# LCD_Joystick.net
KiCad netlist of a schematic drawn in Altium Designer
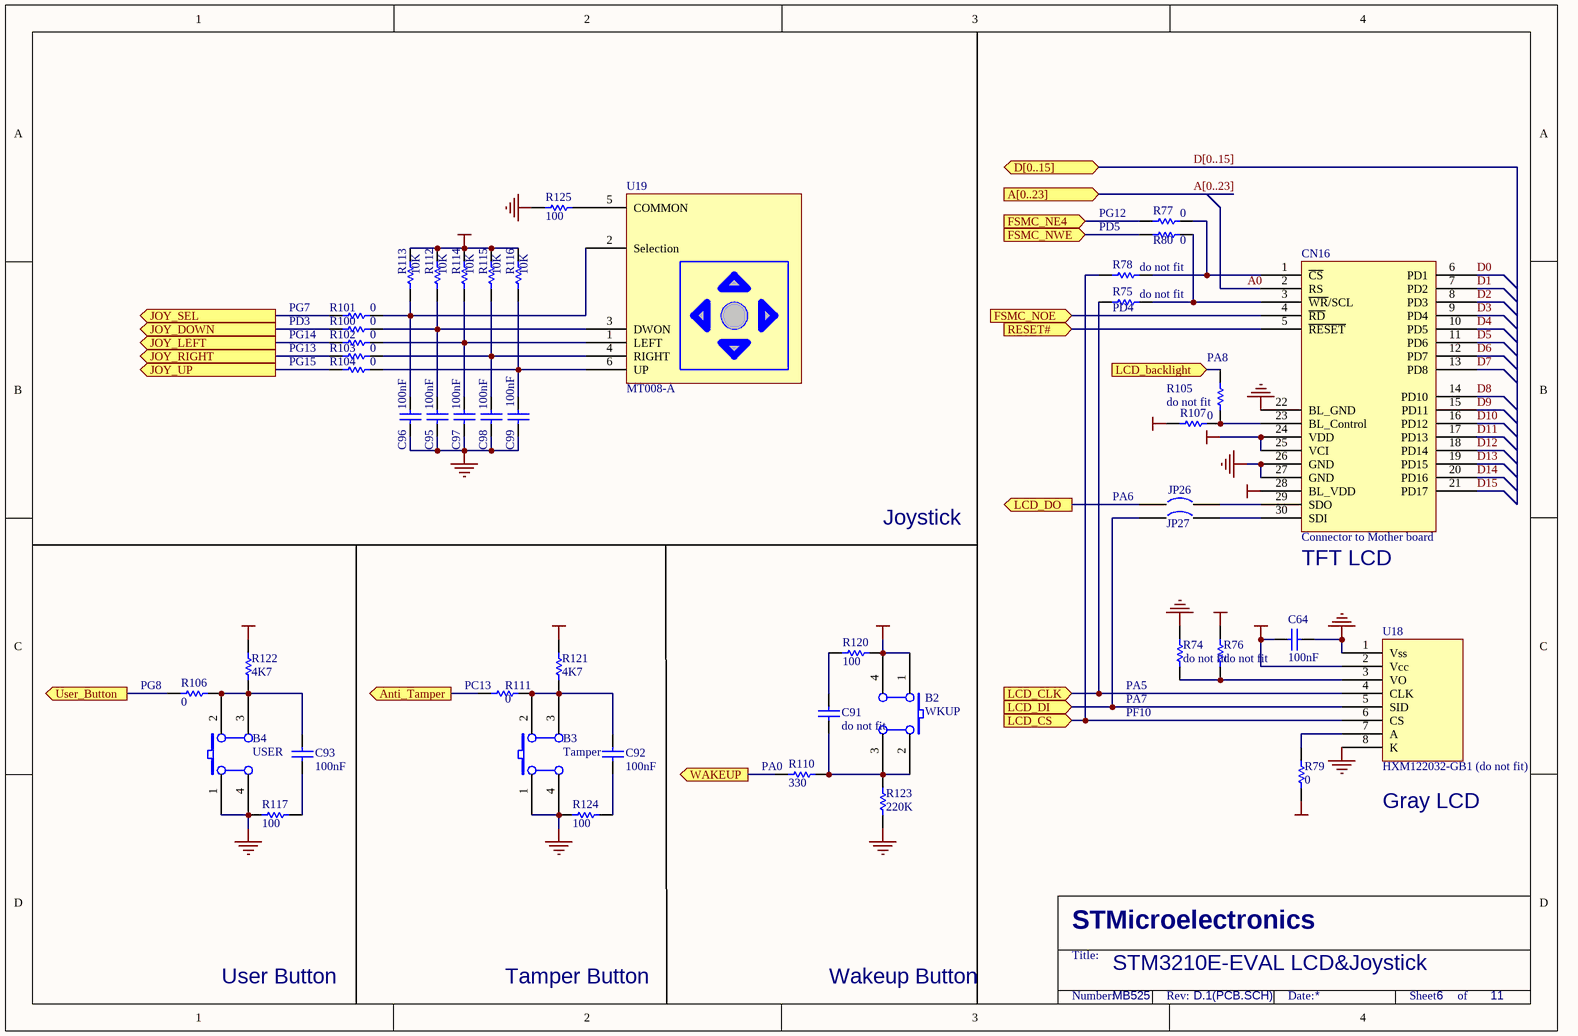
[diagram p0: LCD&Joystick.SchDoc]

(export (version "E")
  (design (tool "Eeschema 10.0.6"))
  (components
    (comp (ref "B2")
      (value "WKUP")
      (footprint "PB10")
      (description "SE PUSHBUTTON")
      (libsource (lib "Documents") (part "SW PUSHBUTTON"))
    )
    (comp (ref "B3")
      (value "Tamper")
      (footprint "PB10")
      (description "SE PUSHBUTTON")
      (libsource (lib "Documents") (part "SW PUSHBUTTON"))
    )
    (comp (ref "B4")
      (value "USER")
      (footprint "PB10")
      (description "SE PUSHBUTTON")
      (libsource (lib "Documents") (part "SW PUSHBUTTON"))
    )
    (comp (ref "C64")
      (value "100nF")
      (description "Capacitor")
      (fields (field (name "PUBLISHER") "Altium Limited"))
      (libsource (lib "Miscellaneous Devices") (part "CAP"))
    )
    (comp (ref "C91")
      (value "do not fit")
      (description "Capacitor")
      (fields (field (name "PUBLISHER") "Altium Limited"))
      (libsource (lib "Miscellaneous Devices") (part "CAP"))
    )
    (comp (ref "C92")
      (value "100nF")
      (description "Capacitor")
      (fields (field (name "PUBLISHER") "Altium Limited"))
      (libsource (lib "Miscellaneous Devices") (part "CAP"))
    )
    (comp (ref "C93")
      (value "100nF")
      (description "Capacitor")
      (fields (field (name "PUBLISHER") "Altium Limited"))
      (libsource (lib "Miscellaneous Devices") (part "CAP"))
    )
    (comp (ref "C95")
      (value "100nF")
      (description "Capacitor")
      (fields (field (name "PUBLISHER") "Altium Limited"))
      (libsource (lib "Miscellaneous Devices") (part "CAP"))
    )
    (comp (ref "C96")
      (value "100nF")
      (description "Capacitor")
      (fields (field (name "PUBLISHER") "Altium Limited"))
      (libsource (lib "Miscellaneous Devices") (part "CAP"))
    )
    (comp (ref "C97")
      (value "100nF")
      (description "Capacitor")
      (fields (field (name "PUBLISHER") "Altium Limited"))
      (libsource (lib "Miscellaneous Devices") (part "CAP"))
    )
    (comp (ref "C98")
      (value "100nF")
      (description "Capacitor")
      (fields (field (name "PUBLISHER") "Altium Limited"))
      (libsource (lib "Miscellaneous Devices") (part "CAP"))
    )
    (comp (ref "C99")
      (value "100nF")
      (description "Capacitor")
      (fields (field (name "PUBLISHER") "Altium Limited"))
      (libsource (lib "Miscellaneous Devices") (part "CAP"))
    )
    (comp (ref "CN16")
      (value "Connector to Mother board")
      (footprint "AM240320A")
      (libsource (lib "MB694") (part "ColorLCD_module"))
    )
    (comp (ref "JP26")
      (value "~")
      (footprint "SPST-2")
      (description "Circuit Breaker")
      (fields (field (name "PUBLISHER") "Altium Limited"))
      (libsource (lib "Miscellaneous Devices") (part "Circuit Breaker"))
    )
    (comp (ref "JP27")
      (value "~")
      (footprint "SPST-2")
      (description "Circuit Breaker")
      (fields (field (name "PUBLISHER") "Altium Limited"))
      (libsource (lib "Miscellaneous Devices") (part "Circuit Breaker"))
    )
    (comp (ref "R74")
      (value "do not fit")
      (description "Resistor")
      (fields (field (name "PUBLISHER") "Altium Limited"))
      (libsource (lib "Miscellaneous Devices") (part "Res1"))
    )
    (comp (ref "R75")
      (value "do not fit")
      (description "Resistor")
      (fields (field (name "PUBLISHER") "Altium Limited"))
      (libsource (lib "Miscellaneous Devices") (part "Res1"))
    )
    (comp (ref "R76")
      (value "do not fit")
      (description "Resistor")
      (fields (field (name "PUBLISHER") "Altium Limited"))
      (libsource (lib "Miscellaneous Devices") (part "Res1"))
    )
    (comp (ref "R77")
      (value "0")
      (description "Resistor")
      (fields (field (name "PUBLISHER") "Altium Limited"))
      (libsource (lib "Miscellaneous Devices") (part "Res1"))
    )
    (comp (ref "R78")
      (value "do not fit")
      (description "Resistor")
      (fields (field (name "PUBLISHER") "Altium Limited"))
      (libsource (lib "Miscellaneous Devices") (part "Res1"))
    )
    (comp (ref "R79")
      (value "0")
      (description "Resistor")
      (fields (field (name "PUBLISHER") "Altium Limited"))
      (libsource (lib "Miscellaneous Devices") (part "Res1"))
    )
    (comp (ref "R80")
      (value "0")
      (description "Resistor")
      (fields (field (name "PUBLISHER") "Altium Limited"))
      (libsource (lib "Miscellaneous Devices") (part "Res1"))
    )
    (comp (ref "R100")
      (value "0")
      (description "Resistor")
      (fields (field (name "PUBLISHER") "Altium Limited"))
      (libsource (lib "Miscellaneous Devices") (part "Res1"))
    )
    (comp (ref "R101")
      (value "0")
      (description "Resistor")
      (fields (field (name "PUBLISHER") "Altium Limited"))
      (libsource (lib "Miscellaneous Devices") (part "Res1"))
    )
    (comp (ref "R102")
      (value "0")
      (description "Resistor")
      (fields (field (name "PUBLISHER") "Altium Limited"))
      (libsource (lib "Miscellaneous Devices") (part "Res1"))
    )
    (comp (ref "R103")
      (value "0")
      (description "Resistor")
      (fields (field (name "PUBLISHER") "Altium Limited"))
      (libsource (lib "Miscellaneous Devices") (part "Res1"))
    )
    (comp (ref "R104")
      (value "0")
      (description "Resistor")
      (fields (field (name "PUBLISHER") "Altium Limited"))
      (libsource (lib "Miscellaneous Devices") (part "Res1"))
    )
    (comp (ref "R105")
      (value "do not fit")
      (description "Resistor")
      (fields (field (name "PUBLISHER") "Altium Limited"))
      (libsource (lib "Miscellaneous Devices") (part "Res1"))
    )
    (comp (ref "R106")
      (value "0")
      (description "Resistor")
      (fields (field (name "PUBLISHER") "Altium Limited"))
      (libsource (lib "Miscellaneous Devices") (part "Res1"))
    )
    (comp (ref "R107")
      (value "0")
      (description "Resistor")
      (fields (field (name "PUBLISHER") "Altium Limited"))
      (libsource (lib "Miscellaneous Devices") (part "Res1"))
    )
    (comp (ref "R110")
      (value "330")
      (description "Resistor")
      (fields (field (name "PUBLISHER") "Altium Limited"))
      (libsource (lib "Miscellaneous Devices") (part "Res1"))
    )
    (comp (ref "R111")
      (value "0")
      (description "Resistor")
      (fields (field (name "PUBLISHER") "Altium Limited"))
      (libsource (lib "Miscellaneous Devices") (part "Res1"))
    )
    (comp (ref "R112")
      (value "10K")
      (description "Resistor")
      (fields (field (name "PUBLISHER") "Altium Limited"))
      (libsource (lib "Miscellaneous Devices") (part "Res1"))
    )
    (comp (ref "R113")
      (value "10K")
      (description "Resistor")
      (fields (field (name "PUBLISHER") "Altium Limited"))
      (libsource (lib "Miscellaneous Devices") (part "Res1"))
    )
    (comp (ref "R114")
      (value "10K")
      (description "Resistor")
      (fields (field (name "PUBLISHER") "Altium Limited"))
      (libsource (lib "Miscellaneous Devices") (part "Res1"))
    )
    (comp (ref "R115")
      (value "10K")
      (description "Resistor")
      (fields (field (name "PUBLISHER") "Altium Limited"))
      (libsource (lib "Miscellaneous Devices") (part "Res1"))
    )
    (comp (ref "R116")
      (value "10K")
      (description "Resistor")
      (fields (field (name "PUBLISHER") "Altium Limited"))
      (libsource (lib "Miscellaneous Devices") (part "Res1"))
    )
    (comp (ref "R117")
      (value "100")
      (description "Resistor")
      (fields (field (name "PUBLISHER") "Altium Limited"))
      (libsource (lib "Miscellaneous Devices") (part "Res1"))
    )
    (comp (ref "R120")
      (value "100")
      (description "Resistor")
      (fields (field (name "PUBLISHER") "Altium Limited"))
      (libsource (lib "Miscellaneous Devices") (part "Res1"))
    )
    (comp (ref "R121")
      (value "4K7")
      (description "Resistor")
      (fields (field (name "PUBLISHER") "Altium Limited"))
      (libsource (lib "Miscellaneous Devices") (part "res1"))
    )
    (comp (ref "R122")
      (value "4K7")
      (description "Resistor")
      (fields (field (name "PUBLISHER") "Altium Limited"))
      (libsource (lib "Miscellaneous Devices") (part "res1"))
    )
    (comp (ref "R123")
      (value "220K")
      (description "Resistor")
      (fields (field (name "PUBLISHER") "Altium Limited"))
      (libsource (lib "Miscellaneous Devices") (part "res1"))
    )
    (comp (ref "R124")
      (value "100")
      (description "Resistor")
      (fields (field (name "PUBLISHER") "Altium Limited"))
      (libsource (lib "Miscellaneous Devices") (part "Res1"))
    )
    (comp (ref "R125")
      (value "100")
      (description "Resistor")
      (fields (field (name "PUBLISHER") "Altium Limited"))
      (libsource (lib "Miscellaneous Devices") (part "Res1"))
    )
    (comp (ref "U18")
      (value "HXM122032-GB1 (do not fit)")
      (footprint "LCD12232-GB1")
      (libsource (lib "MB513") (part "HXM122032-GB1"))
    )
    (comp (ref "U19") (value "MT008-A") (footprint "JOY") (libsource (lib "MB513") (part "MT-008A")))
  )
  (nets
    (net (code "24") (name "+3V3") (class "Default")
      (node (ref "B2") (pin "1") (pinfunction "A0_1") (pintype "passive"))
      (node (ref "B2") (pin "4") (pinfunction "A1_4") (pintype "passive"))
      (node (ref "C64") (pin "1") (pinfunction "1_1") (pintype "passive"))
      (node (ref "CN16") (pin "24") (pinfunction "VDD_24") (pintype "passive"))
      (node (ref "CN16") (pin "25") (pinfunction "VCI_25") (pintype "passive"))
      (node (ref "CN16") (pin "28") (pinfunction "BL_VDD_28") (pintype "passive"))
      (node (ref "R107") (pin "2") (pinfunction "2_2") (pintype "passive"))
      (node (ref "R112") (pin "2") (pinfunction "2_2") (pintype "passive"))
      (node (ref "R113") (pin "1") (pinfunction "1_1") (pintype "passive"))
      (node (ref "R114") (pin "2") (pinfunction "2_2") (pintype "passive"))
      (node (ref "R115") (pin "2") (pinfunction "2_2") (pintype "passive"))
      (node (ref "R116") (pin "2") (pinfunction "2_2") (pintype "passive"))
      (node (ref "R120") (pin "1") (pinfunction "1_1") (pintype "passive"))
      (node (ref "R121") (pin "2") (pinfunction "2_2") (pintype "passive"))
      (node (ref "R122") (pin "2") (pinfunction "2_2") (pintype "passive"))
      (node (ref "R76") (pin "2") (pinfunction "2_2") (pintype "passive"))
      (node (ref "U18") (pin "2") (pinfunction "Vcc_2") (pintype "passive"))
    )
    (net (code "25") (name "+5V") (class "Default")
      (node (ref "R79") (pin "1") (pinfunction "1_1") (pintype "passive"))
    )
    (net (code "26") (name "/A0") (class "Default")
      (node (ref "CN16") (pin "2") (pinfunction "RS_2") (pintype "passive"))
    )
    (net (code "28") (name "/Anti_Tamper") (class "Default")
      (node (ref "R111") (pin "2") (pinfunction "2_2") (pintype "passive"))
    )
    (net (code "29") (name "/D0") (class "Default")
      (node (ref "CN16") (pin "6") (pinfunction "PD1_6") (pintype "passive"))
    )
    (net (code "30") (name "/D1") (class "Default")
      (node (ref "CN16") (pin "7") (pinfunction "PD2_7") (pintype "passive"))
    )
    (net (code "31") (name "/D2") (class "Default")
      (node (ref "CN16") (pin "8") (pinfunction "PD3_8") (pintype "passive"))
    )
    (net (code "32") (name "/D3") (class "Default")
      (node (ref "CN16") (pin "9") (pinfunction "PD4_9") (pintype "passive"))
    )
    (net (code "33") (name "/D4") (class "Default")
      (node (ref "CN16") (pin "10") (pinfunction "PD5_10") (pintype "passive"))
    )
    (net (code "34") (name "/D5") (class "Default")
      (node (ref "CN16") (pin "11") (pinfunction "PD6_11") (pintype "passive"))
    )
    (net (code "35") (name "/D6") (class "Default")
      (node (ref "CN16") (pin "12") (pinfunction "PD7_12") (pintype "passive"))
    )
    (net (code "36") (name "/D7") (class "Default")
      (node (ref "CN16") (pin "13") (pinfunction "PD8_13") (pintype "passive"))
    )
    (net (code "37") (name "/D8") (class "Default")
      (node (ref "CN16") (pin "14") (pinfunction "PD10_14") (pintype "passive"))
    )
    (net (code "38") (name "/D9") (class "Default")
      (node (ref "CN16") (pin "15") (pinfunction "PD11_15") (pintype "passive"))
    )
    (net (code "39") (name "/D10") (class "Default")
      (node (ref "CN16") (pin "16") (pinfunction "PD12_16") (pintype "passive"))
    )
    (net (code "40") (name "/D11") (class "Default")
      (node (ref "CN16") (pin "17") (pinfunction "PD13_17") (pintype "passive"))
    )
    (net (code "41") (name "/D12") (class "Default")
      (node (ref "CN16") (pin "18") (pinfunction "PD14_18") (pintype "passive"))
    )
    (net (code "42") (name "/D13") (class "Default")
      (node (ref "CN16") (pin "19") (pinfunction "PD15_19") (pintype "passive"))
    )
    (net (code "43") (name "/D14") (class "Default")
      (node (ref "CN16") (pin "20") (pinfunction "PD16_20") (pintype "passive"))
    )
    (net (code "44") (name "/D15") (class "Default")
      (node (ref "CN16") (pin "21") (pinfunction "PD17_21") (pintype "passive"))
    )
    (net (code "46") (name "/FSMC_NE4") (class "Default")
      (node (ref "R77") (pin "1") (pinfunction "1_1") (pintype "passive"))
    )
    (net (code "47") (name "/FSMC_NOE") (class "Default")
      (node (ref "CN16") (pin "4") (pinfunction "~{RD}_4") (pintype "passive"))
    )
    (net (code "48") (name "/FSMC_NWE") (class "Default")
      (node (ref "R80") (pin "1") (pinfunction "1_1") (pintype "passive"))
    )
    (net (code "49") (name "/JOY_DOWN") (class "Default")
      (node (ref "R100") (pin "2") (pinfunction "2_2") (pintype "passive"))
    )
    (net (code "50") (name "/JOY_LEFT") (class "Default")
      (node (ref "R102") (pin "2") (pinfunction "2_2") (pintype "passive"))
    )
    (net (code "51") (name "/JOY_RIGHT") (class "Default")
      (node (ref "R103") (pin "2") (pinfunction "2_2") (pintype "passive"))
    )
    (net (code "52") (name "/JOY_SEL") (class "Default")
      (node (ref "R101") (pin "2") (pinfunction "2_2") (pintype "passive"))
    )
    (net (code "53") (name "/JOY_UP") (class "Default")
      (node (ref "R104") (pin "2") (pinfunction "2_2") (pintype "passive"))
    )
    (net (code "54") (name "/LCD_CLK") (class "Default")
      (node (ref "R75") (pin "2") (pinfunction "2_2") (pintype "passive"))
      (node (ref "U18") (pin "4") (pinfunction "CLK_4") (pintype "passive"))
    )
    (net (code "55") (name "/LCD_CS") (class "Default")
      (node (ref "R78") (pin "1") (pinfunction "1_1") (pintype "passive"))
      (node (ref "U18") (pin "6") (pinfunction "CS_6") (pintype "passive"))
    )
    (net (code "56") (name "/LCD_DI") (class "Default")
      (node (ref "JP27") (pin "1") (pinfunction "1_1") (pintype "passive"))
      (node (ref "U18") (pin "5") (pinfunction "SID_5") (pintype "passive"))
    )
    (net (code "57") (name "/LCD_DO") (class "Default")
      (node (ref "JP26") (pin "1") (pinfunction "1_1") (pintype "passive"))
    )
    (net (code "58") (name "/LCD_backlight") (class "Default")
      (node (ref "R105") (pin "2") (pinfunction "2_2") (pintype "passive"))
    )
    (net (code "59") (name "/RESET#") (class "Default")
      (node (ref "CN16") (pin "5") (pinfunction "~{RESET}_5") (pintype "passive"))
    )
    (net (code "60") (name "/User_Button") (class "Default")
      (node (ref "R106") (pin "2") (pinfunction "2_2") (pintype "passive"))
    )
    (net (code "61") (name "/WAKEUP") (class "Default")
      (node (ref "R110") (pin "2") (pinfunction "2_2") (pintype "passive"))
    )
    (net (code "62") (name "GND") (class "Default")
      (node (ref "B3") (pin "1") (pinfunction "A0_1") (pintype "passive"))
      (node (ref "B3") (pin "4") (pinfunction "A1_4") (pintype "passive"))
      (node (ref "B4") (pin "1") (pinfunction "A0_1") (pintype "passive"))
      (node (ref "B4") (pin "4") (pinfunction "A1_4") (pintype "passive"))
      (node (ref "C64") (pin "2") (pinfunction "2_2") (pintype "passive"))
      (node (ref "C95") (pin "1") (pinfunction "1_1") (pintype "passive"))
      (node (ref "C96") (pin "1") (pinfunction "1_1") (pintype "passive"))
      (node (ref "C97") (pin "1") (pinfunction "1_1") (pintype "passive"))
      (node (ref "C98") (pin "1") (pinfunction "1_1") (pintype "passive"))
      (node (ref "C99") (pin "1") (pinfunction "1_1") (pintype "passive"))
      (node (ref "CN16") (pin "22") (pinfunction "BL_GND_22") (pintype "passive"))
      (node (ref "CN16") (pin "26") (pinfunction "GND_26") (pintype "passive"))
      (node (ref "CN16") (pin "27") (pinfunction "GND_27") (pintype "passive"))
      (node (ref "R117") (pin "1") (pinfunction "1_1") (pintype "passive"))
      (node (ref "R123") (pin "2") (pinfunction "2_2") (pintype "passive"))
      (node (ref "R124") (pin "1") (pinfunction "1_1") (pintype "passive"))
      (node (ref "R125") (pin "1") (pinfunction "1_1") (pintype "passive"))
      (node (ref "R74") (pin "1") (pinfunction "1_1") (pintype "passive"))
      (node (ref "U18") (pin "1") (pinfunction "Vss_1") (pintype "passive"))
      (node (ref "U18") (pin "8") (pinfunction "K_8") (pintype "passive"))
    )
    (net (code "63") (name "Net-(B2-B0)") (class "Default")
      (node (ref "B2") (pin "2") (pinfunction "B0_2") (pintype "passive"))
      (node (ref "B2") (pin "3") (pinfunction "B1_3") (pintype "passive"))
      (node (ref "C91") (pin "2") (pinfunction "2_2") (pintype "passive"))
      (node (ref "R110") (pin "1") (pinfunction "1_1") (pintype "passive"))
      (node (ref "R123") (pin "1") (pinfunction "1_1") (pintype "passive"))
    )
    (net (code "64") (name "Net-(B3-B0)") (class "Default")
      (node (ref "B3") (pin "2") (pinfunction "B0_2") (pintype "passive"))
      (node (ref "B3") (pin "3") (pinfunction "B1_3") (pintype "passive"))
      (node (ref "C92") (pin "2") (pinfunction "2_2") (pintype "passive"))
      (node (ref "R111") (pin "1") (pinfunction "1_1") (pintype "passive"))
      (node (ref "R121") (pin "1") (pinfunction "1_1") (pintype "passive"))
    )
    (net (code "65") (name "Net-(B4-B0)") (class "Default")
      (node (ref "B4") (pin "2") (pinfunction "B0_2") (pintype "passive"))
      (node (ref "B4") (pin "3") (pinfunction "B1_3") (pintype "passive"))
      (node (ref "C93") (pin "2") (pinfunction "2_2") (pintype "passive"))
      (node (ref "R106") (pin "1") (pinfunction "1_1") (pintype "passive"))
      (node (ref "R122") (pin "1") (pinfunction "1_1") (pintype "passive"))
    )
    (net (code "66") (name "Net-(C91-Pad1)") (class "Default")
      (node (ref "C91") (pin "1") (pinfunction "1_1") (pintype "passive"))
      (node (ref "R120") (pin "2") (pinfunction "2_2") (pintype "passive"))
    )
    (net (code "67") (name "Net-(C92-Pad1)") (class "Default")
      (node (ref "C92") (pin "1") (pinfunction "1_1") (pintype "passive"))
      (node (ref "R124") (pin "2") (pinfunction "2_2") (pintype "passive"))
    )
    (net (code "68") (name "Net-(C93-Pad1)") (class "Default")
      (node (ref "C93") (pin "1") (pinfunction "1_1") (pintype "passive"))
      (node (ref "R117") (pin "2") (pinfunction "2_2") (pintype "passive"))
    )
    (net (code "69") (name "Net-(CN16-BL_Control)") (class "Default")
      (node (ref "CN16") (pin "23") (pinfunction "BL_Control_23") (pintype "passive"))
      (node (ref "R105") (pin "1") (pinfunction "1_1") (pintype "passive"))
      (node (ref "R107") (pin "1") (pinfunction "1_1") (pintype "passive"))
    )
    (net (code "70") (name "Net-(CN16-SDI)") (class "Default")
      (node (ref "CN16") (pin "30") (pinfunction "SDI_30") (pintype "passive"))
      (node (ref "JP27") (pin "2") (pinfunction "2_2") (pintype "passive"))
    )
    (net (code "71") (name "Net-(CN16-SDO)") (class "Default")
      (node (ref "CN16") (pin "29") (pinfunction "SDO_29") (pintype "passive"))
      (node (ref "JP26") (pin "2") (pinfunction "2_2") (pintype "passive"))
    )
    (net (code "72") (name "Net-(CN16-~{CS})") (class "Default")
      (node (ref "CN16") (pin "1") (pinfunction "~{CS}_1") (pintype "passive"))
      (node (ref "R77") (pin "2") (pinfunction "2_2") (pintype "passive"))
      (node (ref "R78") (pin "2") (pinfunction "2_2") (pintype "passive"))
    )
    (net (code "73") (name "Net-(CN16-~{WR}{slash}SCL)") (class "Default")
      (node (ref "CN16") (pin "3") (pinfunction "~{WR}/SCL_3") (pintype "passive"))
      (node (ref "R75") (pin "1") (pinfunction "1_1") (pintype "passive"))
      (node (ref "R80") (pin "2") (pinfunction "2_2") (pintype "passive"))
    )
    (net (code "74") (name "Net-(U18-A)") (class "Default")
      (node (ref "R79") (pin "2") (pinfunction "2_2") (pintype "passive"))
      (node (ref "U18") (pin "7") (pinfunction "A_7") (pintype "passive"))
    )
    (net (code "75") (name "Net-(U18-VO)") (class "Default")
      (node (ref "R74") (pin "2") (pinfunction "2_2") (pintype "passive"))
      (node (ref "R76") (pin "1") (pinfunction "1_1") (pintype "passive"))
      (node (ref "U18") (pin "3") (pinfunction "VO_3") (pintype "passive"))
    )
    (net (code "76") (name "Net-(U19-COMMON)") (class "Default")
      (node (ref "R125") (pin "2") (pinfunction "2_2") (pintype "passive"))
      (node (ref "U19") (pin "5") (pinfunction "COMMON_5") (pintype "passive"))
    )
    (net (code "77") (name "Net-(U19-DWON)") (class "Default")
      (node (ref "C95") (pin "2") (pinfunction "2_2") (pintype "passive"))
      (node (ref "R100") (pin "1") (pinfunction "1_1") (pintype "passive"))
      (node (ref "R112") (pin "1") (pinfunction "1_1") (pintype "passive"))
      (node (ref "U19") (pin "3") (pinfunction "DWON_3") (pintype "passive"))
    )
    (net (code "78") (name "Net-(U19-LEFT)") (class "Default")
      (node (ref "C97") (pin "2") (pinfunction "2_2") (pintype "passive"))
      (node (ref "R102") (pin "1") (pinfunction "1_1") (pintype "passive"))
      (node (ref "R114") (pin "1") (pinfunction "1_1") (pintype "passive"))
      (node (ref "U19") (pin "1") (pinfunction "LEFT_1") (pintype "passive"))
    )
    (net (code "79") (name "Net-(U19-RIGHT)") (class "Default")
      (node (ref "C98") (pin "2") (pinfunction "2_2") (pintype "passive"))
      (node (ref "R103") (pin "1") (pinfunction "1_1") (pintype "passive"))
      (node (ref "R115") (pin "1") (pinfunction "1_1") (pintype "passive"))
      (node (ref "U19") (pin "4") (pinfunction "RIGHT_4") (pintype "passive"))
    )
    (net (code "80") (name "Net-(U19-Selection)") (class "Default")
      (node (ref "C96") (pin "2") (pinfunction "2_2") (pintype "passive"))
      (node (ref "R101") (pin "1") (pinfunction "1_1") (pintype "passive"))
      (node (ref "R113") (pin "2") (pinfunction "2_2") (pintype "passive"))
      (node (ref "U19") (pin "2") (pinfunction "Selection_2") (pintype "passive"))
    )
    (net (code "81") (name "Net-(U19-UP)") (class "Default")
      (node (ref "C99") (pin "2") (pinfunction "2_2") (pintype "passive"))
      (node (ref "R104") (pin "1") (pinfunction "1_1") (pintype "passive"))
      (node (ref "R116") (pin "1") (pinfunction "1_1") (pintype "passive"))
      (node (ref "U19") (pin "6") (pinfunction "UP_6") (pintype "passive"))
    )
  )
)
